# Buck_Converter.net
KiCad netlist of a schematic drawn in Altium Designer
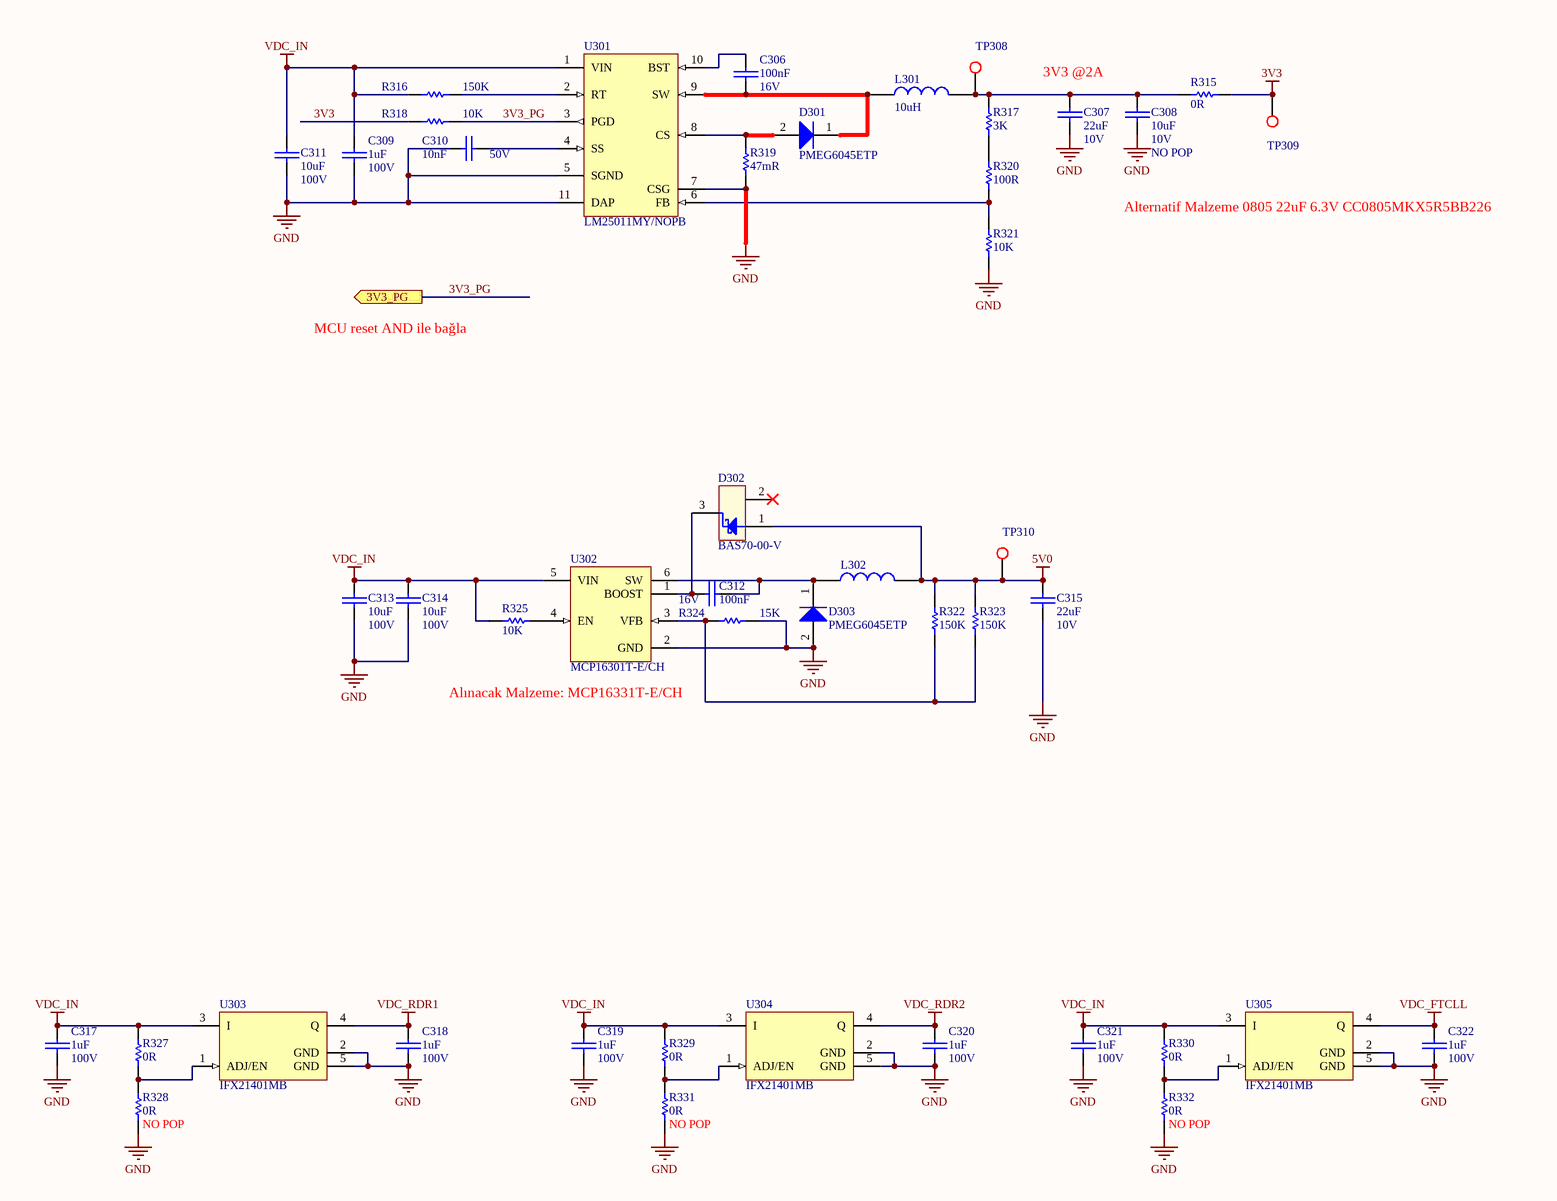
[diagram p0: Buck_Converter.SchDoc]

(export (version "E")
  (design (tool "Eeschema 10.0.6"))
  (components
    (comp (ref "C306")
      (value "100nF")
      (footprint "CAPC1005X06N")
      (description "CAP, CER, X7R, 100nF, %10, 16V, 0402")
      (fields
        (field (name "MANUFACTURER") "Murata")
        (field (name "MANUFACTURER PART NUMBER") "GRM155R71C104KA88D")
        (field (name "OPERATING VOLTAGE") "16V")
      )
      (libsource (lib "Anime_Capacitor") (part "ACC7-2100-S241-0000"))
    )
    (comp (ref "C307")
      (value "22uF")
      (footprint "CAPC3225X27N")
      (description "CAP, CER, X7R, 22uF, %20, 10V, 1210")
      (fields
        (field (name "MANUFACTURER") "Murata")
        (field (name "MANUFACTURER PART NUMBER") "GRM32ER71A226KE20L")
        (field (name "OPERATING VOLTAGE") "10V")
      )
      (libsource (lib "Anime_Capacitor") (part "ACC7-4220-S730-0000"))
    )
    (comp (ref "C308")
      (value "10uF")
      (footprint "CAPC2012X09N")
      (description "CAP, CER, X7R, 10uF, %10, 10V, 0805")
      (fields
        (field (name "MANUFACTURER") "Murata")
        (field (name "MANUFACTURER PART NUMBER") "GRM21BR71A106KE51L")
        (field (name "OPERATING VOLTAGE") "10V")
        (field (name "ASSEMBLY") "NO POP")
      )
      (libsource (lib "Anime_Capacitor") (part "ACC7-4100-S431-0000"))
    )
    (comp (ref "C309")
      (value "1uF")
      (footprint "CAPC3216X09N")
      (description "CAP, CER, X7R, 1uF, %10, 100V, 1206")
      (fields
        (field (name "MANUFACTURER") "Murata")
        (field (name "MANUFACTURER PART NUMBER") "GRM31CR72A105KA01L")
        (field (name "OPERATING VOLTAGE") "100V")
      )
      (libsource (lib "Anime_Capacitor") (part "ACC7-3100-S691-0000"))
    )
    (comp (ref "C310")
      (value "10nF")
      (footprint "CAPC1005X06N")
      (description "CAP, CER, X7R, 10nF, %10, 50V, 0402")
      (fields
        (field (name "MANUFACTURER") "Murata")
        (field (name "MANUFACTURER PART NUMBER") "GRM155R71H103KA88D")
        (field (name "OPERATING VOLTAGE") "50V")
      )
      (libsource (lib "Anime_Capacitor") (part "ACC7-1100-S271-0000"))
    )
    (comp (ref "C311")
      (value "10uF")
      (footprint "CAPC5750X25N")
      (description "CAP, CER, X7S, 10uF, %10, 100V, 2220")
      (fields
        (field (name "MANUFACTURER") "TDK")
        (field (name "MANUFACTURER PART NUMBER") "CGA9N3X7S2A106K230KB")
        (field (name "OPERATING VOLTAGE") "100V")
      )
      (libsource (lib "Anime_Capacitor") (part "ACC4-4100-SD91-0000"))
    )
    (comp (ref "C312")
      (value "100nF")
      (footprint "CAPC1005X06N")
      (description "CAP, CER, X7R, 100nF, %10, 16V, 0402")
      (fields
        (field (name "MANUFACTURER") "Murata")
        (field (name "MANUFACTURER PART NUMBER") "GRM155R71C104KA88D")
        (field (name "OPERATING VOLTAGE") "16V")
      )
      (libsource (lib "Anime_Capacitor") (part "ACC7-2100-S241-0000"))
    )
    (comp (ref "C313")
      (value "10uF")
      (footprint "CAPC5750X25N")
      (description "CAP, CER, X7S, 10uF, %10, 100V, 2220")
      (fields
        (field (name "MANUFACTURER") "TDK")
        (field (name "MANUFACTURER PART NUMBER") "CGA9N3X7S2A106K230KB")
        (field (name "OPERATING VOLTAGE") "100V")
      )
      (libsource (lib "Anime_Capacitor") (part "ACC4-4100-SD91-0000"))
    )
    (comp (ref "C314")
      (value "10uF")
      (footprint "CAPC5750X25N")
      (description "CAP, CER, X7S, 10uF, %10, 100V, 2220")
      (fields
        (field (name "MANUFACTURER") "TDK")
        (field (name "MANUFACTURER PART NUMBER") "CGA9N3X7S2A106K230KB")
        (field (name "OPERATING VOLTAGE") "100V")
      )
      (libsource (lib "Anime_Capacitor") (part "ACC4-4100-SD91-0000"))
    )
    (comp (ref "C315")
      (value "22uF")
      (footprint "CAPC3225X27N")
      (description "CAP, CER, X7R, 22uF, %20, 10V, 1210")
      (fields
        (field (name "MANUFACTURER") "Murata")
        (field (name "MANUFACTURER PART NUMBER") "GRM32ER71A226KE20L")
        (field (name "OPERATING VOLTAGE") "10V")
      )
      (libsource (lib "Anime_Capacitor") (part "ACC7-4220-S730-0000"))
    )
    (comp (ref "C317")
      (value "1uF")
      (footprint "CAPC3216X09N")
      (description "CAP, CER, X7R, 1uF, %10, 100V, 1206")
      (fields
        (field (name "MANUFACTURER") "Murata")
        (field (name "MANUFACTURER PART NUMBER") "GRM31CR72A105KA01L")
        (field (name "OPERATING VOLTAGE") "100V")
      )
      (libsource (lib "Anime_Capacitor") (part "ACC7-3100-S691-0000"))
    )
    (comp (ref "C318")
      (value "1uF")
      (footprint "CAPC3216X09N")
      (description "CAP, CER, X7R, 1uF, %10, 100V, 1206")
      (fields
        (field (name "MANUFACTURER") "Murata")
        (field (name "MANUFACTURER PART NUMBER") "GRM31CR72A105KA01L")
        (field (name "OPERATING VOLTAGE") "100V")
      )
      (libsource (lib "Anime_Capacitor") (part "ACC7-3100-S691-0000"))
    )
    (comp (ref "C319")
      (value "1uF")
      (footprint "CAPC3216X09N")
      (description "CAP, CER, X7R, 1uF, %10, 100V, 1206")
      (fields
        (field (name "MANUFACTURER") "Murata")
        (field (name "MANUFACTURER PART NUMBER") "GRM31CR72A105KA01L")
        (field (name "OPERATING VOLTAGE") "100V")
      )
      (libsource (lib "Anime_Capacitor") (part "ACC7-3100-S691-0000"))
    )
    (comp (ref "C320")
      (value "1uF")
      (footprint "CAPC3216X09N")
      (description "CAP, CER, X7R, 1uF, %10, 100V, 1206")
      (fields
        (field (name "MANUFACTURER") "Murata")
        (field (name "MANUFACTURER PART NUMBER") "GRM31CR72A105KA01L")
        (field (name "OPERATING VOLTAGE") "100V")
      )
      (libsource (lib "Anime_Capacitor") (part "ACC7-3100-S691-0000"))
    )
    (comp (ref "C321")
      (value "1uF")
      (footprint "CAPC3216X09N")
      (description "CAP, CER, X7R, 1uF, %10, 100V, 1206")
      (fields
        (field (name "MANUFACTURER") "Murata")
        (field (name "MANUFACTURER PART NUMBER") "GRM31CR72A105KA01L")
        (field (name "OPERATING VOLTAGE") "100V")
      )
      (libsource (lib "Anime_Capacitor") (part "ACC7-3100-S691-0000"))
    )
    (comp (ref "C322")
      (value "1uF")
      (footprint "CAPC3216X09N")
      (description "CAP, CER, X7R, 1uF, %10, 100V, 1206")
      (fields
        (field (name "MANUFACTURER") "Murata")
        (field (name "MANUFACTURER PART NUMBER") "GRM31CR72A105KA01L")
        (field (name "OPERATING VOLTAGE") "100V")
      )
      (libsource (lib "Anime_Capacitor") (part "ACC7-3100-S691-0000"))
    )
    (comp (ref "D301")
      (value "PMEG6045ETP")
      (footprint "DIOM3825X11N")
      (description "Diode, Schottky, 0.53V @4.5A, 60V, SOD-128")
      (fields (field (name "MANUFACTURER") "NXP"))
      (libsource (lib "Anime_Semiconductor") (part "AS15-945M-SI10-0000"))
    )
    (comp (ref "D302")
      (value "BAS70-00-V")
      (footprint "SOT90P247X115-3N")
      (description "Diode, Schottky, 0.41V @1mA, BAS70-00-V, SOT23")
      (fields (field (name "MANUFACTURER") "VISHAY"))
      (libsource (lib "Anime_Semiconductor") (part "AS15-820M-SI20-0002"))
    )
    (comp (ref "D303")
      (value "PMEG6045ETP")
      (footprint "DIOM3825X11N")
      (description "Diode, Schottky, 0.53V @4.5A, 60V, SOD-128")
      (fields (field (name "MANUFACTURER") "NXP"))
      (libsource (lib "Anime_Semiconductor") (part "AS15-945M-SI10-0000"))
    )
    (comp (ref "L301")
      (value "10uH")
      (footprint "INDM125125X65N")
      (description "Inductor, Power, 10uH, 5.5A, 20mohm, SMD")
      (fields (field (name "MANUFACTURER") "Bourns") (field (name "MANUFACTURER PART NUMBER") "SRR1260-100M"))
      (libsource (lib "Anime_Inductor") (part "AL17-1000-SN35-3550"))
    )
    (comp (ref "L302")
      (value "~")
      (footprint "INDM125125X65N")
      (description "Inductor, Power, 22uH, 4A, 43 mohm, SMD")
      (fields (field (name "MANUFACTURER") "Bourns") (field (name "MANUFACTURER PART NUMBER") "SRR1260-220M"))
      (libsource (lib "Anime_Inductor") (part "AL17-2200-SN35-3400"))
    )
    (comp (ref "R315")
      (value "0R")
      (footprint "RESC2012X07N")
      (description "RES, Thick Film, SMD, 0R, Jumper, 0.125W, 0805")
      (fields
        (field (name "MANUFACTURER") "Panasonic")
        (field (name "MANUFACTURER PART NUMBER") "ERJ-6GEY0R00V")
      )
      (libsource (lib "Anime_Resistor") (part "AR19-0000-S407-0000"))
    )
    (comp (ref "R316")
      (value "150K")
      (footprint "RESC1005X04N")
      (description "RES, E24, Thick Film, SMD, 150K, 1%, 0.1W, 0402")
      (fields
        (field (name "MANUFACTURER") "Panasonic")
        (field (name "MANUFACTURER PART NUMBER") "ERJ-2RKF1503X")
      )
      (libsource (lib "Anime_Resistor") (part "AR19-5150-S2B2-0000"))
    )
    (comp (ref "R317")
      (value "3K")
      (footprint "RESC1005X04N")
      (description "RES, E24, Thick Film, SMD, 3K, 1%, 0.1W, 0402")
      (fields
        (field (name "MANUFACTURER") "Panasonic")
        (field (name "MANUFACTURER PART NUMBER") "ERJ-2RKF3001X")
      )
      (libsource (lib "Anime_Resistor") (part "AR19-3300-S2B2-0000"))
    )
    (comp (ref "R318")
      (value "10K")
      (footprint "RESC1005X04N")
      (description "RES, E24, Thick Film, SMD, 10K, 1%, 0.1W, 0402")
      (fields
        (field (name "MANUFACTURER") "Panasonic")
        (field (name "MANUFACTURER PART NUMBER") "ERJ-2RKF1002X")
      )
      (libsource (lib "Anime_Resistor") (part "AR19-4100-S2B2-0000"))
    )
    (comp (ref "R319")
      (value "47mR")
      (footprint "RESC3216X08N")
      (description "RES, Thick Film, SMD, 47mR, 1%, 1W, 1206")
      (fields
        (field (name "MANUFACTURER") "Panasonic")
        (field (name "MANUFACTURER PART NUMBER") "ERJ-8BWFR047V")
      )
      (libsource (lib "Anime_Resistor") (part "AR19-Y470-S5D2-0000"))
    )
    (comp (ref "R320")
      (value "100R")
      (footprint "RESC1005X04N")
      (description "RES, E24, Thick Film, SMD, 100R, 1%, 0.1W, 0402")
      (fields
        (field (name "MANUFACTURER") "Panasonic")
        (field (name "MANUFACTURER PART NUMBER") "ERJ-2RKF1000X")
      )
      (libsource (lib "Anime_Resistor") (part "AR19-2100-S2B2-0000"))
    )
    (comp (ref "R321")
      (value "10K")
      (footprint "RESC1005X04N")
      (description "RES, E24, Thick Film, SMD, 10K, 1%, 0.1W, 0402")
      (fields
        (field (name "MANUFACTURER") "Panasonic")
        (field (name "MANUFACTURER PART NUMBER") "ERJ-2RKF1002X")
      )
      (libsource (lib "Anime_Resistor") (part "AR19-4100-S2B2-0000"))
    )
    (comp (ref "R322")
      (value "150K")
      (footprint "RESC1005X04N")
      (description "RES, E24, Thick Film, SMD, 150K, 1%, 0.1W, 0402")
      (fields
        (field (name "MANUFACTURER") "Panasonic")
        (field (name "MANUFACTURER PART NUMBER") "ERJ-2RKF1503X")
      )
      (libsource (lib "Anime_Resistor") (part "AR19-5150-S2B2-0000"))
    )
    (comp (ref "R323")
      (value "150K")
      (footprint "RESC1005X04N")
      (description "RES, E24, Thick Film, SMD, 150K, 1%, 0.1W, 0402")
      (fields
        (field (name "MANUFACTURER") "Panasonic")
        (field (name "MANUFACTURER PART NUMBER") "ERJ-2RKF1503X")
      )
      (libsource (lib "Anime_Resistor") (part "AR19-5150-S2B2-0000"))
    )
    (comp (ref "R324")
      (value "15K")
      (footprint "RESC1005X04N")
      (description "RES, E24, Thick Film, SMD, 15K, 1%, 0.1W, 0402")
      (fields
        (field (name "MANUFACTURER") "Panasonic")
        (field (name "MANUFACTURER PART NUMBER") "ERJ-2RKF1502X")
      )
      (libsource (lib "Anime_Resistor") (part "AR19-4150-S2B2-0000"))
    )
    (comp (ref "R325")
      (value "10K")
      (footprint "RESC1005X04N")
      (description "RES, E24, Thick Film, SMD, 10K, 1%, 0.1W, 0402")
      (fields
        (field (name "MANUFACTURER") "Panasonic")
        (field (name "MANUFACTURER PART NUMBER") "ERJ-2RKF1002X")
      )
      (libsource (lib "Anime_Resistor") (part "AR19-4100-S2B2-0000"))
    )
    (comp (ref "R327")
      (value "0R")
      (footprint "RESC1005X04N")
      (description "RES, Thick Film, SMD, 0R, Jumper, 0.1W, 0402")
      (fields
        (field (name "MANUFACTURER") "Panasonic")
        (field (name "MANUFACTURER PART NUMBER") "ERJ-2GE0R00X")
      )
      (libsource (lib "Anime_Resistor") (part "AR19-0000-S201-0000"))
    )
    (comp (ref "R328")
      (value "0R")
      (footprint "RESC1005X04N")
      (description "RES, Thick Film, SMD, 0R, Jumper, 0.1W, 0402")
      (fields
        (field (name "MANUFACTURER") "Panasonic")
        (field (name "MANUFACTURER PART NUMBER") "ERJ-2GE0R00X")
        (field (name "ASSEMBLY") "NO POP")
      )
      (libsource (lib "Anime_Resistor") (part "AR19-0000-S201-0000"))
    )
    (comp (ref "R329")
      (value "0R")
      (footprint "RESC1005X04N")
      (description "RES, Thick Film, SMD, 0R, Jumper, 0.1W, 0402")
      (fields
        (field (name "MANUFACTURER") "Panasonic")
        (field (name "MANUFACTURER PART NUMBER") "ERJ-2GE0R00X")
      )
      (libsource (lib "Anime_Resistor") (part "AR19-0000-S201-0000"))
    )
    (comp (ref "R330")
      (value "0R")
      (footprint "RESC1005X04N")
      (description "RES, Thick Film, SMD, 0R, Jumper, 0.1W, 0402")
      (fields
        (field (name "MANUFACTURER") "Panasonic")
        (field (name "MANUFACTURER PART NUMBER") "ERJ-2GE0R00X")
      )
      (libsource (lib "Anime_Resistor") (part "AR19-0000-S201-0000"))
    )
    (comp (ref "R331")
      (value "0R")
      (footprint "RESC1005X04N")
      (description "RES, Thick Film, SMD, 0R, Jumper, 0.1W, 0402")
      (fields
        (field (name "MANUFACTURER") "Panasonic")
        (field (name "MANUFACTURER PART NUMBER") "ERJ-2GE0R00X")
        (field (name "ASSEMBLY") "NO POP")
      )
      (libsource (lib "Anime_Resistor") (part "AR19-0000-S201-0000"))
    )
    (comp (ref "R332")
      (value "0R")
      (footprint "RESC1005X04N")
      (description "RES, Thick Film, SMD, 0R, Jumper, 0.1W, 0402")
      (fields
        (field (name "MANUFACTURER") "Panasonic")
        (field (name "MANUFACTURER PART NUMBER") "ERJ-2GE0R00X")
        (field (name "ASSEMBLY") "NO POP")
      )
      (libsource (lib "Anime_Resistor") (part "AR19-0000-S201-0000"))
    )
    (comp (ref "TP308")
      (value "AEMT-C00S-1000-0000")
      (footprint "TP100")
      (description "Test Point, Circular, 1mm")
      (libsource (lib "Anime_Electromechanical") (part "AEMT-C00S-1000-0000"))
    )
    (comp (ref "TP309")
      (value "AEMT-C00S-1000-0000")
      (footprint "TP100")
      (description "Test Point, Circular, 1mm")
      (libsource (lib "Anime_Electromechanical") (part "AEMT-C00S-1000-0000"))
    )
    (comp (ref "TP310")
      (value "AEMT-C00S-1000-0000")
      (footprint "TP100")
      (description "Test Point, Circular, 1mm")
      (libsource (lib "Anime_Electromechanical") (part "AEMT-C00S-1000-0000"))
    )
    (comp (ref "U301")
      (value "LM25011MY/NOPB")
      (footprint "MUC10A_N")
      (description "42V, 2A Constant On-Time Switching Regulator with Adjustable Current Limit, 10-pin eMSOP, Pb-Free")
      (fields (field (name "MANUFACTURER") "National Semiconductor"))
      (libsource (lib "National Semiconductor Switcher") (part "LM25011MY/NOPB"))
    )
    (comp (ref "U302")
      (value "MCP16301T-E/CH")
      (footprint "MCHP-SOT-23-CH6_N")
      (fields (field (name "MANUFACTURER") "Microchip"))
      (libsource (lib "Microchip Power Management Switching Regulator") (part "MCP16301T-E/CH"))
    )
    (comp (ref "U303")
      (value "IFX21401MB")
      (footprint "INF-PG-SCT595_V")
      (fields (field (name "MANUFACTURER") "Infineon"))
      (libsource (lib "Infineon_Power_Supply_Voltage_Regulator") (part "IFX21401MB"))
    )
    (comp (ref "U304")
      (value "IFX21401MB")
      (footprint "INF-PG-SCT595_V")
      (fields (field (name "MANUFACTURER") "Infineon"))
      (libsource (lib "Infineon_Power_Supply_Voltage_Regulator") (part "IFX21401MB"))
    )
    (comp (ref "U305")
      (value "IFX21401MB")
      (footprint "INF-PG-SCT595_V")
      (fields (field (name "MANUFACTURER") "Infineon"))
      (libsource (lib "Infineon_Power_Supply_Voltage_Regulator") (part "IFX21401MB"))
    )
  )
  (nets
    (net (code "1") (name "/3V3_PG") (class "Default")
      (node (ref "R318") (pin "1") (pinfunction "1_1") (pintype "passive"))
      (node (ref "U301") (pin "3") (pinfunction "PGD_3") (pintype "output"))
    )
    (net (code "2") (name "3V3") (class "Default")
      (node (ref "R315") (pin "2") (pinfunction "2_2") (pintype "passive"))
      (node (ref "R318") (pin "2") (pinfunction "2_2") (pintype "passive"))
      (node (ref "TP309") (pin "1") (pintype "passive"))
    )
    (net (code "3") (name "5V0") (class "Default")
      (node (ref "C315") (pin "2") (pintype "passive"))
      (node (ref "D302") (pin "1") (pinfunction "1_1") (pintype "passive"))
      (node (ref "L302") (pin "2") (pinfunction "2_2") (pintype "passive"))
      (node (ref "R322") (pin "2") (pinfunction "2_2") (pintype "passive"))
      (node (ref "R323") (pin "2") (pinfunction "2_2") (pintype "passive"))
      (node (ref "TP310") (pin "1") (pintype "passive"))
    )
    (net (code "4") (name "GND") (class "Default")
      (node (ref "C307") (pin "1") (pintype "passive"))
      (node (ref "C308") (pin "1") (pintype "passive"))
      (node (ref "C309") (pin "1") (pintype "passive"))
      (node (ref "C310") (pin "1") (pintype "passive"))
      (node (ref "C311") (pin "1") (pintype "passive"))
      (node (ref "C313") (pin "1") (pintype "passive"))
      (node (ref "C314") (pin "1") (pintype "passive"))
      (node (ref "C315") (pin "1") (pintype "passive"))
      (node (ref "C317") (pin "1") (pintype "passive"))
      (node (ref "C318") (pin "1") (pintype "passive"))
      (node (ref "C319") (pin "1") (pintype "passive"))
      (node (ref "C320") (pin "1") (pintype "passive"))
      (node (ref "C321") (pin "1") (pintype "passive"))
      (node (ref "C322") (pin "1") (pintype "passive"))
      (node (ref "D303") (pin "2") (pinfunction "A_2") (pintype "passive"))
      (node (ref "R319") (pin "2") (pinfunction "2_2") (pintype "passive"))
      (node (ref "R321") (pin "1") (pinfunction "1_1") (pintype "passive"))
      (node (ref "R324") (pin "1") (pinfunction "1_1") (pintype "passive"))
      (node (ref "R328") (pin "1") (pinfunction "1_1") (pintype "passive"))
      (node (ref "R331") (pin "1") (pinfunction "1_1") (pintype "passive"))
      (node (ref "R332") (pin "1") (pinfunction "1_1") (pintype "passive"))
      (node (ref "U301") (pin "11") (pinfunction "DAP_11") (pintype "power_in"))
      (node (ref "U301") (pin "5") (pinfunction "SGND_5") (pintype "power_in"))
      (node (ref "U301") (pin "7") (pinfunction "CSG_7") (pintype "power_in"))
      (node (ref "U302") (pin "2") (pinfunction "GND_2") (pintype "power_in"))
      (node (ref "U303") (pin "2") (pinfunction "GND_2") (pintype "power_in"))
      (node (ref "U303") (pin "5") (pinfunction "GND_5") (pintype "power_in"))
      (node (ref "U304") (pin "2") (pinfunction "GND_2") (pintype "power_in"))
      (node (ref "U304") (pin "5") (pinfunction "GND_5") (pintype "power_in"))
      (node (ref "U305") (pin "2") (pinfunction "GND_2") (pintype "power_in"))
      (node (ref "U305") (pin "5") (pinfunction "GND_5") (pintype "power_in"))
    )
    (net (code "5") (name "Net-(C307-Pad2)") (class "Default")
      (node (ref "C307") (pin "2") (pintype "passive"))
      (node (ref "C308") (pin "2") (pintype "passive"))
      (node (ref "L301") (pin "2") (pinfunction "2_2") (pintype "passive"))
      (node (ref "R315") (pin "1") (pinfunction "1_1") (pintype "passive"))
      (node (ref "R317") (pin "2") (pinfunction "2_2") (pintype "passive"))
      (node (ref "TP308") (pin "1") (pintype "passive"))
    )
    (net (code "6") (name "Net-(D301-A)") (class "Default")
      (node (ref "D301") (pin "2") (pinfunction "A_2") (pintype "passive"))
      (node (ref "R319") (pin "1") (pinfunction "1_1") (pintype "passive"))
      (node (ref "U301") (pin "8") (pinfunction "CS_8") (pintype "input"))
    )
    (net (code "7") (name "Net-(D301-K)") (class "Default")
      (node (ref "C306") (pin "1") (pintype "passive"))
      (node (ref "D301") (pin "1") (pinfunction "K_1") (pintype "passive"))
      (node (ref "L301") (pin "1") (pinfunction "1_1") (pintype "passive"))
      (node (ref "U301") (pin "9") (pinfunction "SW_9") (pintype "input"))
    )
    (net (code "8") (name "Net-(D303-K)") (class "Default")
      (node (ref "C312") (pin "1") (pintype "passive"))
      (node (ref "D303") (pin "1") (pinfunction "K_1") (pintype "passive"))
      (node (ref "L302") (pin "1") (pinfunction "1_1") (pintype "passive"))
      (node (ref "U302") (pin "6") (pinfunction "SW_6") (pintype "power_in"))
    )
    (net (code "9") (name "Net-(R317-Pad1)") (class "Default")
      (node (ref "R317") (pin "1") (pinfunction "1_1") (pintype "passive"))
      (node (ref "R320") (pin "1") (pinfunction "1_1") (pintype "passive"))
    )
    (net (code "10") (name "Net-(U301-BST)") (class "Default")
      (node (ref "C306") (pin "2") (pintype "passive"))
      (node (ref "U301") (pin "10") (pinfunction "BST_10") (pintype "input"))
    )
    (net (code "11") (name "Net-(U301-FB)") (class "Default")
      (node (ref "R320") (pin "2") (pinfunction "2_2") (pintype "passive"))
      (node (ref "R321") (pin "2") (pinfunction "2_2") (pintype "passive"))
      (node (ref "U301") (pin "6") (pinfunction "FB_6") (pintype "input"))
    )
    (net (code "12") (name "Net-(U301-RT)") (class "Default")
      (node (ref "R316") (pin "1") (pinfunction "1_1") (pintype "passive"))
      (node (ref "U301") (pin "2") (pinfunction "RT_2") (pintype "input"))
    )
    (net (code "13") (name "Net-(U301-SS)") (class "Default")
      (node (ref "C310") (pin "2") (pintype "passive"))
      (node (ref "U301") (pin "4") (pinfunction "SS_4") (pintype "input"))
    )
    (net (code "14") (name "Net-(U302-BOOST)") (class "Default")
      (node (ref "C312") (pin "2") (pintype "passive"))
      (node (ref "D302") (pin "3") (pinfunction "3_3") (pintype "passive"))
      (node (ref "U302") (pin "1") (pinfunction "BOOST_1") (pintype "power_in"))
    )
    (net (code "15") (name "Net-(U302-EN)") (class "Default")
      (node (ref "R325") (pin "2") (pinfunction "2_2") (pintype "passive"))
      (node (ref "U302") (pin "4") (pinfunction "EN_4") (pintype "input"))
    )
    (net (code "16") (name "Net-(U302-VFB)") (class "Default")
      (node (ref "R322") (pin "1") (pinfunction "1_1") (pintype "passive"))
      (node (ref "R323") (pin "1") (pinfunction "1_1") (pintype "passive"))
      (node (ref "R324") (pin "2") (pinfunction "2_2") (pintype "passive"))
      (node (ref "U302") (pin "3") (pinfunction "VFB_3") (pintype "input"))
    )
    (net (code "17") (name "Net-(U303-ADJ{slash}EN)") (class "Default")
      (node (ref "R327") (pin "1") (pinfunction "1_1") (pintype "passive"))
      (node (ref "R328") (pin "2") (pinfunction "2_2") (pintype "passive"))
      (node (ref "U303") (pin "1") (pinfunction "ADJ/EN_1") (pintype "input"))
    )
    (net (code "18") (name "Net-(U304-ADJ{slash}EN)") (class "Default")
      (node (ref "R329") (pin "1") (pinfunction "1_1") (pintype "passive"))
      (node (ref "R331") (pin "2") (pinfunction "2_2") (pintype "passive"))
      (node (ref "U304") (pin "1") (pinfunction "ADJ/EN_1") (pintype "input"))
    )
    (net (code "19") (name "Net-(U305-ADJ{slash}EN)") (class "Default")
      (node (ref "R330") (pin "1") (pinfunction "1_1") (pintype "passive"))
      (node (ref "R332") (pin "2") (pinfunction "2_2") (pintype "passive"))
      (node (ref "U305") (pin "1") (pinfunction "ADJ/EN_1") (pintype "input"))
    )
    (net (code "20") (name "VDC_FTCLL") (class "Default")
      (node (ref "C322") (pin "2") (pintype "passive"))
      (node (ref "U305") (pin "4") (pinfunction "Q_4") (pintype "power_in"))
    )
    (net (code "21") (name "VDC_IN") (class "Default")
      (node (ref "C309") (pin "2") (pintype "passive"))
      (node (ref "C311") (pin "2") (pintype "passive"))
      (node (ref "C313") (pin "2") (pintype "passive"))
      (node (ref "C314") (pin "2") (pintype "passive"))
      (node (ref "C317") (pin "2") (pintype "passive"))
      (node (ref "C319") (pin "2") (pintype "passive"))
      (node (ref "C321") (pin "2") (pintype "passive"))
      (node (ref "R316") (pin "2") (pinfunction "2_2") (pintype "passive"))
      (node (ref "R325") (pin "1") (pinfunction "1_1") (pintype "passive"))
      (node (ref "R327") (pin "2") (pinfunction "2_2") (pintype "passive"))
      (node (ref "R329") (pin "2") (pinfunction "2_2") (pintype "passive"))
      (node (ref "R330") (pin "2") (pinfunction "2_2") (pintype "passive"))
      (node (ref "U301") (pin "1") (pinfunction "VIN_1") (pintype "power_in"))
      (node (ref "U302") (pin "5") (pinfunction "VIN_5") (pintype "power_in"))
      (node (ref "U303") (pin "3") (pinfunction "I_3") (pintype "power_in"))
      (node (ref "U304") (pin "3") (pinfunction "I_3") (pintype "power_in"))
      (node (ref "U305") (pin "3") (pinfunction "I_3") (pintype "power_in"))
    )
    (net (code "22") (name "VDC_RDR1") (class "Default")
      (node (ref "C318") (pin "2") (pintype "passive"))
      (node (ref "U303") (pin "4") (pinfunction "Q_4") (pintype "power_in"))
    )
    (net (code "23") (name "VDC_RDR2") (class "Default")
      (node (ref "C320") (pin "2") (pintype "passive"))
      (node (ref "U304") (pin "4") (pinfunction "Q_4") (pintype "power_in"))
    )
    (net (code "24") (name "unconnected-(D302-NC-Pad2)") (class "Default")
      (node (ref "D302") (pin "2") (pinfunction "NC_2") (pintype "passive+no_connect"))
    )
  )
)
